# voltagereference.net
KiCad netlist of a schematic drawn in EAGLE
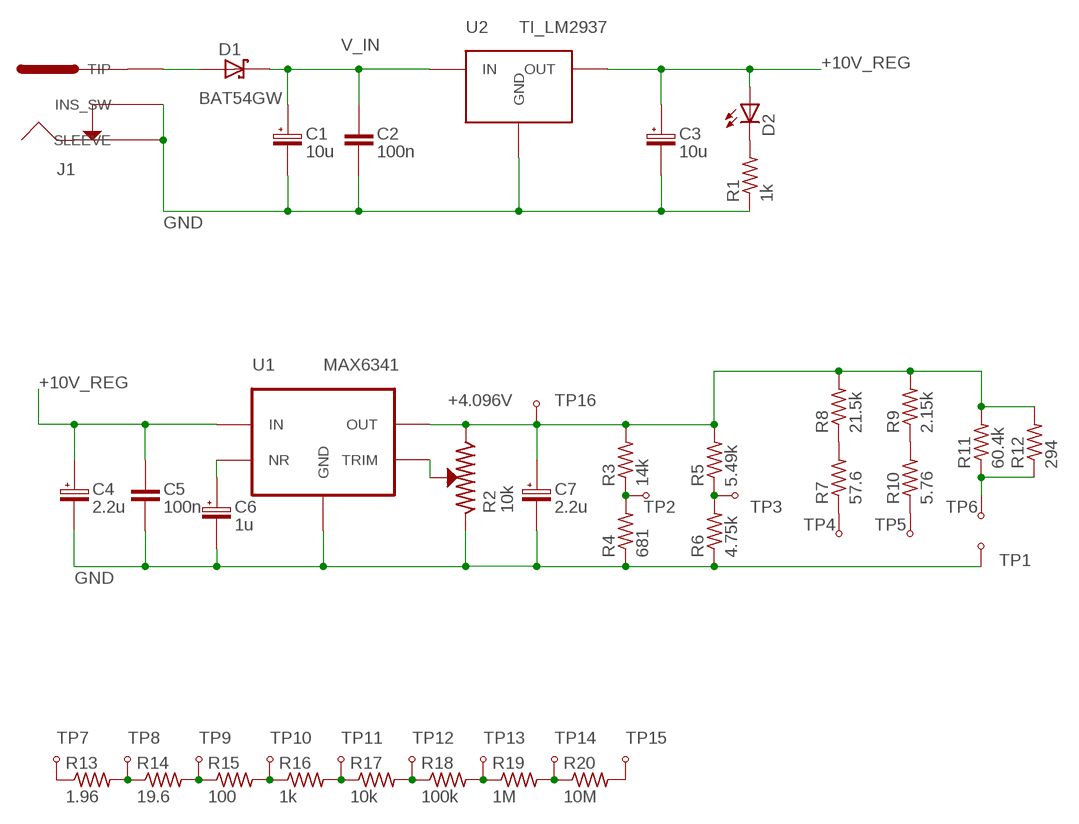
[diagram p0: schematic, sheet 1]

(export (version "E")
  (design (tool "Eeschema 10.0.6"))
  (components
    (comp (ref "C1")
      (value "10u")
      (footprint "eagle-import:PANASONIC_EEE_4MM")
      (libsource (lib "eagle-import") (part "PANASONIC_EEE_4MM"))
    )
    (comp (ref "C2")
      (value "100n")
      (footprint "eagle-import:0805")
      (libsource (lib "eagle-import") (part "C_0805"))
    )
    (comp (ref "C3")
      (value "10u")
      (footprint "eagle-import:PANASONIC_EEE_4MM")
      (libsource (lib "eagle-import") (part "PANASONIC_EEE_4MM"))
    )
    (comp (ref "C4")
      (value "2.2u")
      (footprint "eagle-import:PANASONIC_EEE_4MM")
      (libsource (lib "eagle-import") (part "PANASONIC_EEE_4MM"))
    )
    (comp (ref "C5")
      (value "100n")
      (footprint "eagle-import:0805")
      (libsource (lib "eagle-import") (part "C_0805"))
    )
    (comp (ref "C6")
      (value "1u")
      (footprint "eagle-import:PANASONIC_EEE_4MM")
      (libsource (lib "eagle-import") (part "PANASONIC_EEE_4MM"))
    )
    (comp (ref "C7")
      (value "2.2u")
      (footprint "eagle-import:PANASONIC_EEE_4MM")
      (libsource (lib "eagle-import") (part "PANASONIC_EEE_4MM"))
    )
    (comp (ref "D1")
      (value "BAT54GW")
      (footprint "eagle-import:SOD123_NEX")
      (libsource (lib "eagle-import") (part "NEX_BAT54GW"))
    )
    (comp (ref "D2")
      (value "LED_0805")
      (footprint "eagle-import:0805_POL")
      (libsource (lib "eagle-import") (part "LED_0805"))
    )
    (comp (ref "J1")
      (value "KOBICONN_163-179PH-EX")
      (footprint "eagle-import:KOBICONN_163-179PH-EX")
      (libsource (lib "eagle-import") (part "KOBICONN_163-179PH-EX"))
    )
    (comp (ref "R1")
      (value "1k")
      (footprint "eagle-import:0805")
      (libsource (lib "eagle-import") (part "R_0805"))
    )
    (comp (ref "R2")
      (value "10k")
      (footprint "eagle-import:BOURNS_3224X")
      (libsource (lib "eagle-import") (part "BOURNS_3224X"))
    )
    (comp (ref "R3")
      (value "14k")
      (footprint "eagle-import:0805")
      (libsource (lib "eagle-import") (part "R_0805"))
    )
    (comp (ref "R4")
      (value "681")
      (footprint "eagle-import:0805")
      (libsource (lib "eagle-import") (part "R_0805"))
    )
    (comp (ref "R5")
      (value "5.49k")
      (footprint "eagle-import:0805")
      (libsource (lib "eagle-import") (part "R_0805"))
    )
    (comp (ref "R6")
      (value "4.75k")
      (footprint "eagle-import:0805")
      (libsource (lib "eagle-import") (part "R_0805"))
    )
    (comp (ref "R7")
      (value "57.6")
      (footprint "eagle-import:0805")
      (libsource (lib "eagle-import") (part "R_0805"))
    )
    (comp (ref "R8")
      (value "21.5k")
      (footprint "eagle-import:0805")
      (libsource (lib "eagle-import") (part "R_0805"))
    )
    (comp (ref "R9")
      (value "2.15k")
      (footprint "eagle-import:0805")
      (libsource (lib "eagle-import") (part "R_0805"))
    )
    (comp (ref "R10")
      (value "5.76")
      (footprint "eagle-import:0805")
      (libsource (lib "eagle-import") (part "R_0805"))
    )
    (comp (ref "R11")
      (value "60.4k")
      (footprint "eagle-import:0805")
      (libsource (lib "eagle-import") (part "R_0805"))
    )
    (comp (ref "R12")
      (value "294")
      (footprint "eagle-import:0805")
      (libsource (lib "eagle-import") (part "R_0805"))
    )
    (comp (ref "R13")
      (value "1.96")
      (footprint "eagle-import:0603")
      (libsource (lib "eagle-import") (part "R_0603"))
    )
    (comp (ref "R14")
      (value "19.6")
      (footprint "eagle-import:0603")
      (libsource (lib "eagle-import") (part "R_0603"))
    )
    (comp (ref "R15")
      (value "100")
      (footprint "eagle-import:0805")
      (libsource (lib "eagle-import") (part "R_0805"))
    )
    (comp (ref "R16")
      (value "1k")
      (footprint "eagle-import:0805")
      (libsource (lib "eagle-import") (part "R_0805"))
    )
    (comp (ref "R17")
      (value "10k")
      (footprint "eagle-import:0805")
      (libsource (lib "eagle-import") (part "R_0805"))
    )
    (comp (ref "R18")
      (value "100k")
      (footprint "eagle-import:0805")
      (libsource (lib "eagle-import") (part "R_0805"))
    )
    (comp (ref "R19")
      (value "1M")
      (footprint "eagle-import:0805")
      (libsource (lib "eagle-import") (part "R_0805"))
    )
    (comp (ref "R20")
      (value "10M")
      (footprint "eagle-import:0805")
      (libsource (lib "eagle-import") (part "R_0805"))
    )
    (comp (ref "TP1")
      (value "KEYSTONE_500X")
      (footprint "eagle-import:KEYSTONE_500X")
      (libsource (lib "eagle-import") (part "KEYSTONE_500X"))
    )
    (comp (ref "TP2")
      (value "KEYSTONE_500X")
      (footprint "eagle-import:KEYSTONE_500X")
      (libsource (lib "eagle-import") (part "KEYSTONE_500X"))
    )
    (comp (ref "TP3")
      (value "KEYSTONE_500X")
      (footprint "eagle-import:KEYSTONE_500X")
      (libsource (lib "eagle-import") (part "KEYSTONE_500X"))
    )
    (comp (ref "TP4")
      (value "KEYSTONE_500X")
      (footprint "eagle-import:KEYSTONE_500X")
      (libsource (lib "eagle-import") (part "KEYSTONE_500X"))
    )
    (comp (ref "TP5")
      (value "KEYSTONE_500X")
      (footprint "eagle-import:KEYSTONE_500X")
      (libsource (lib "eagle-import") (part "KEYSTONE_500X"))
    )
    (comp (ref "TP6")
      (value "KEYSTONE_500X")
      (footprint "eagle-import:KEYSTONE_500X")
      (libsource (lib "eagle-import") (part "KEYSTONE_500X"))
    )
    (comp (ref "TP7")
      (value "KEYSTONE_500X")
      (footprint "eagle-import:KEYSTONE_500X")
      (libsource (lib "eagle-import") (part "KEYSTONE_500X"))
    )
    (comp (ref "TP8")
      (value "KEYSTONE_500X")
      (footprint "eagle-import:KEYSTONE_500X")
      (libsource (lib "eagle-import") (part "KEYSTONE_500X"))
    )
    (comp (ref "TP9")
      (value "KEYSTONE_500X")
      (footprint "eagle-import:KEYSTONE_500X")
      (libsource (lib "eagle-import") (part "KEYSTONE_500X"))
    )
    (comp (ref "TP10")
      (value "KEYSTONE_500X")
      (footprint "eagle-import:KEYSTONE_500X")
      (libsource (lib "eagle-import") (part "KEYSTONE_500X"))
    )
    (comp (ref "TP11")
      (value "KEYSTONE_500X")
      (footprint "eagle-import:KEYSTONE_500X")
      (libsource (lib "eagle-import") (part "KEYSTONE_500X"))
    )
    (comp (ref "TP12")
      (value "KEYSTONE_500X")
      (footprint "eagle-import:KEYSTONE_500X")
      (libsource (lib "eagle-import") (part "KEYSTONE_500X"))
    )
    (comp (ref "TP13")
      (value "KEYSTONE_500X")
      (footprint "eagle-import:KEYSTONE_500X")
      (libsource (lib "eagle-import") (part "KEYSTONE_500X"))
    )
    (comp (ref "TP14")
      (value "KEYSTONE_500X")
      (footprint "eagle-import:KEYSTONE_500X")
      (libsource (lib "eagle-import") (part "KEYSTONE_500X"))
    )
    (comp (ref "TP15")
      (value "KEYSTONE_500X")
      (footprint "eagle-import:KEYSTONE_500X")
      (libsource (lib "eagle-import") (part "KEYSTONE_500X"))
    )
    (comp (ref "TP16")
      (value "KEYSTONE_500X")
      (footprint "eagle-import:KEYSTONE_500X")
      (libsource (lib "eagle-import") (part "KEYSTONE_500X"))
    )
    (comp (ref "U1")
      (value "MAX6341")
      (footprint "eagle-import:SO8_MAX")
      (libsource (lib "eagle-import") (part "MAXIM_MAX6341"))
    )
    (comp (ref "U2")
      (value "TI_LM2937")
      (footprint "eagle-import:SOT223_TI")
      (libsource (lib "eagle-import") (part "TI_LM2937"))
    )
  )
  (nets
    (net (code "1") (name "/+4.096V") (class "Default")
      (node (ref "C7") (pin "P$1") (pinfunction "1_P$1") (pintype "passive"))
      (node (ref "R11") (pin "P$2") (pinfunction "2_P$2") (pintype "passive"))
      (node (ref "R12") (pin "P$2") (pinfunction "2_P$2") (pintype "passive"))
      (node (ref "R2") (pin "P$1") (pinfunction "1_P$1") (pintype "passive"))
      (node (ref "R3") (pin "P$2") (pinfunction "2_P$2") (pintype "passive"))
      (node (ref "R5") (pin "P$2") (pinfunction "2_P$2") (pintype "passive"))
      (node (ref "R8") (pin "P$2") (pinfunction "2_P$2") (pintype "passive"))
      (node (ref "R9") (pin "P$2") (pinfunction "2_P$2") (pintype "passive"))
      (node (ref "TP16") (pin "P$1") (pinfunction "TP_P$1") (pintype "passive"))
      (node (ref "U1") (pin "P$6") (pinfunction "OUT_P$6") (pintype "output"))
    )
    (net (code "2") (name "/+10V_REG") (class "Default")
      (node (ref "C3") (pin "P$1") (pinfunction "1_P$1") (pintype "passive"))
      (node (ref "C4") (pin "P$1") (pinfunction "1_P$1") (pintype "passive"))
      (node (ref "C5") (pin "P$1") (pinfunction "1_P$1") (pintype "passive"))
      (node (ref "D2") (pin "P$1") (pinfunction "A_P$1") (pintype "passive"))
      (node (ref "U1") (pin "P$2") (pinfunction "IN_P$2") (pintype "power_in"))
      (node (ref "U2") (pin "P$3") (pinfunction "OUT_P$3") (pintype "power_in"))
    )
    (net (code "3") (name "/GND") (class "Default")
      (node (ref "C1") (pin "P$2") (pinfunction "2_P$2") (pintype "passive"))
      (node (ref "C2") (pin "P$2") (pinfunction "2_P$2") (pintype "passive"))
      (node (ref "C3") (pin "P$2") (pinfunction "2_P$2") (pintype "passive"))
      (node (ref "C4") (pin "P$2") (pinfunction "2_P$2") (pintype "passive"))
      (node (ref "C5") (pin "P$2") (pinfunction "2_P$2") (pintype "passive"))
      (node (ref "C6") (pin "P$2") (pinfunction "2_P$2") (pintype "passive"))
      (node (ref "C7") (pin "P$2") (pinfunction "2_P$2") (pintype "passive"))
      (node (ref "J1") (pin "P$2") (pinfunction "SLEEVE_P$2") (pintype "power_in"))
      (node (ref "J1") (pin "P$3") (pinfunction "INS_SW_P$3") (pintype "passive"))
      (node (ref "J1") (pin "P$5") (pinfunction "SLEEVE_P$5") (pintype "power_in"))
      (node (ref "J1") (pin "P$6") (pinfunction "INS_SW_P$6") (pintype "passive"))
      (node (ref "R1") (pin "P$1") (pinfunction "1_P$1") (pintype "passive"))
      (node (ref "R2") (pin "P$3") (pinfunction "3_P$3") (pintype "passive"))
      (node (ref "R4") (pin "P$1") (pinfunction "1_P$1") (pintype "passive"))
      (node (ref "R6") (pin "P$1") (pinfunction "1_P$1") (pintype "passive"))
      (node (ref "TP1") (pin "P$1") (pinfunction "TP_P$1") (pintype "passive"))
      (node (ref "U1") (pin "P$4") (pinfunction "GND_P$4") (pintype "power_in"))
      (node (ref "U2") (pin "P$2") (pinfunction "GND_P$2") (pintype "power_in"))
      (node (ref "U2") (pin "P$4") (pinfunction "GND_P$4") (pintype "power_in"))
    )
    (net (code "4") (name "/V_IN") (class "Default")
      (node (ref "C1") (pin "P$1") (pinfunction "1_P$1") (pintype "passive"))
      (node (ref "C2") (pin "P$1") (pinfunction "1_P$1") (pintype "passive"))
      (node (ref "D1") (pin "P$2") (pinfunction "C_P$2") (pintype "passive"))
      (node (ref "U2") (pin "P$1") (pinfunction "IN_P$1") (pintype "power_in"))
    )
    (net (code "5") (name "Net-(C6-1)") (class "Default")
      (node (ref "C6") (pin "P$1") (pinfunction "1_P$1") (pintype "passive"))
      (node (ref "U1") (pin "P$3") (pinfunction "NR_P$3") (pintype "passive"))
    )
    (net (code "6") (name "Net-(D1-A)") (class "Default")
      (node (ref "D1") (pin "P$1") (pinfunction "A_P$1") (pintype "passive"))
      (node (ref "J1") (pin "P$1") (pinfunction "TIP_P$1") (pintype "power_in"))
      (node (ref "J1") (pin "P$4") (pinfunction "TIP_P$4") (pintype "power_in"))
    )
    (net (code "7") (name "Net-(D2-C)") (class "Default")
      (node (ref "D2") (pin "P$2") (pinfunction "C_P$2") (pintype "passive"))
      (node (ref "R1") (pin "P$2") (pinfunction "2_P$2") (pintype "passive"))
    )
    (net (code "8") (name "Net-(R2-2)") (class "Default")
      (node (ref "R2") (pin "P$2") (pinfunction "2_P$2") (pintype "passive"))
      (node (ref "U1") (pin "P$5") (pinfunction "TRIM_P$5") (pintype "passive"))
    )
    (net (code "9") (name "Net-(R3-1)") (class "Default")
      (node (ref "R3") (pin "P$1") (pinfunction "1_P$1") (pintype "passive"))
      (node (ref "R4") (pin "P$2") (pinfunction "2_P$2") (pintype "passive"))
      (node (ref "TP2") (pin "P$1") (pinfunction "TP_P$1") (pintype "passive"))
    )
    (net (code "10") (name "Net-(R5-1)") (class "Default")
      (node (ref "R5") (pin "P$1") (pinfunction "1_P$1") (pintype "passive"))
      (node (ref "R6") (pin "P$2") (pinfunction "2_P$2") (pintype "passive"))
      (node (ref "TP3") (pin "P$1") (pinfunction "TP_P$1") (pintype "passive"))
    )
    (net (code "11") (name "Net-(R7-1)") (class "Default")
      (node (ref "R7") (pin "P$1") (pinfunction "1_P$1") (pintype "passive"))
      (node (ref "TP4") (pin "P$1") (pinfunction "TP_P$1") (pintype "passive"))
    )
    (net (code "12") (name "Net-(R7-2)") (class "Default")
      (node (ref "R7") (pin "P$2") (pinfunction "2_P$2") (pintype "passive"))
      (node (ref "R8") (pin "P$1") (pinfunction "1_P$1") (pintype "passive"))
    )
    (net (code "13") (name "Net-(R10-1)") (class "Default")
      (node (ref "R10") (pin "P$1") (pinfunction "1_P$1") (pintype "passive"))
      (node (ref "TP5") (pin "P$1") (pinfunction "TP_P$1") (pintype "passive"))
    )
    (net (code "14") (name "Net-(R10-2)") (class "Default")
      (node (ref "R10") (pin "P$2") (pinfunction "2_P$2") (pintype "passive"))
      (node (ref "R9") (pin "P$1") (pinfunction "1_P$1") (pintype "passive"))
    )
    (net (code "15") (name "Net-(R11-1)") (class "Default")
      (node (ref "R11") (pin "P$1") (pinfunction "1_P$1") (pintype "passive"))
      (node (ref "R12") (pin "P$1") (pinfunction "1_P$1") (pintype "passive"))
      (node (ref "TP6") (pin "P$1") (pinfunction "TP_P$1") (pintype "passive"))
    )
    (net (code "16") (name "Net-(R13-1)") (class "Default")
      (node (ref "R13") (pin "P$1") (pinfunction "1_P$1") (pintype "passive"))
      (node (ref "TP7") (pin "P$1") (pinfunction "TP_P$1") (pintype "passive"))
    )
    (net (code "17") (name "Net-(R13-2)") (class "Default")
      (node (ref "R13") (pin "P$2") (pinfunction "2_P$2") (pintype "passive"))
      (node (ref "R14") (pin "P$1") (pinfunction "1_P$1") (pintype "passive"))
      (node (ref "TP8") (pin "P$1") (pinfunction "TP_P$1") (pintype "passive"))
    )
    (net (code "18") (name "Net-(R14-2)") (class "Default")
      (node (ref "R14") (pin "P$2") (pinfunction "2_P$2") (pintype "passive"))
      (node (ref "R15") (pin "P$1") (pinfunction "1_P$1") (pintype "passive"))
      (node (ref "TP9") (pin "P$1") (pinfunction "TP_P$1") (pintype "passive"))
    )
    (net (code "19") (name "Net-(R15-2)") (class "Default")
      (node (ref "R15") (pin "P$2") (pinfunction "2_P$2") (pintype "passive"))
      (node (ref "R16") (pin "P$1") (pinfunction "1_P$1") (pintype "passive"))
      (node (ref "TP10") (pin "P$1") (pinfunction "TP_P$1") (pintype "passive"))
    )
    (net (code "20") (name "Net-(R16-2)") (class "Default")
      (node (ref "R16") (pin "P$2") (pinfunction "2_P$2") (pintype "passive"))
      (node (ref "R17") (pin "P$1") (pinfunction "1_P$1") (pintype "passive"))
      (node (ref "TP11") (pin "P$1") (pinfunction "TP_P$1") (pintype "passive"))
    )
    (net (code "21") (name "Net-(R17-2)") (class "Default")
      (node (ref "R17") (pin "P$2") (pinfunction "2_P$2") (pintype "passive"))
      (node (ref "R18") (pin "P$1") (pinfunction "1_P$1") (pintype "passive"))
      (node (ref "TP12") (pin "P$1") (pinfunction "TP_P$1") (pintype "passive"))
    )
    (net (code "22") (name "Net-(R18-2)") (class "Default")
      (node (ref "R18") (pin "P$2") (pinfunction "2_P$2") (pintype "passive"))
      (node (ref "R19") (pin "P$1") (pinfunction "1_P$1") (pintype "passive"))
      (node (ref "TP13") (pin "P$1") (pinfunction "TP_P$1") (pintype "passive"))
    )
    (net (code "23") (name "Net-(R19-2)") (class "Default")
      (node (ref "R19") (pin "P$2") (pinfunction "2_P$2") (pintype "passive"))
      (node (ref "R20") (pin "P$1") (pinfunction "1_P$1") (pintype "passive"))
      (node (ref "TP14") (pin "P$1") (pinfunction "TP_P$1") (pintype "passive"))
    )
    (net (code "24") (name "Net-(R20-2)") (class "Default")
      (node (ref "R20") (pin "P$2") (pinfunction "2_P$2") (pintype "passive"))
      (node (ref "TP15") (pin "P$1") (pinfunction "TP_P$1") (pintype "passive"))
    )
  )
)
